# Alim.net
KiCad netlist of a schematic drawn in Altium Designer
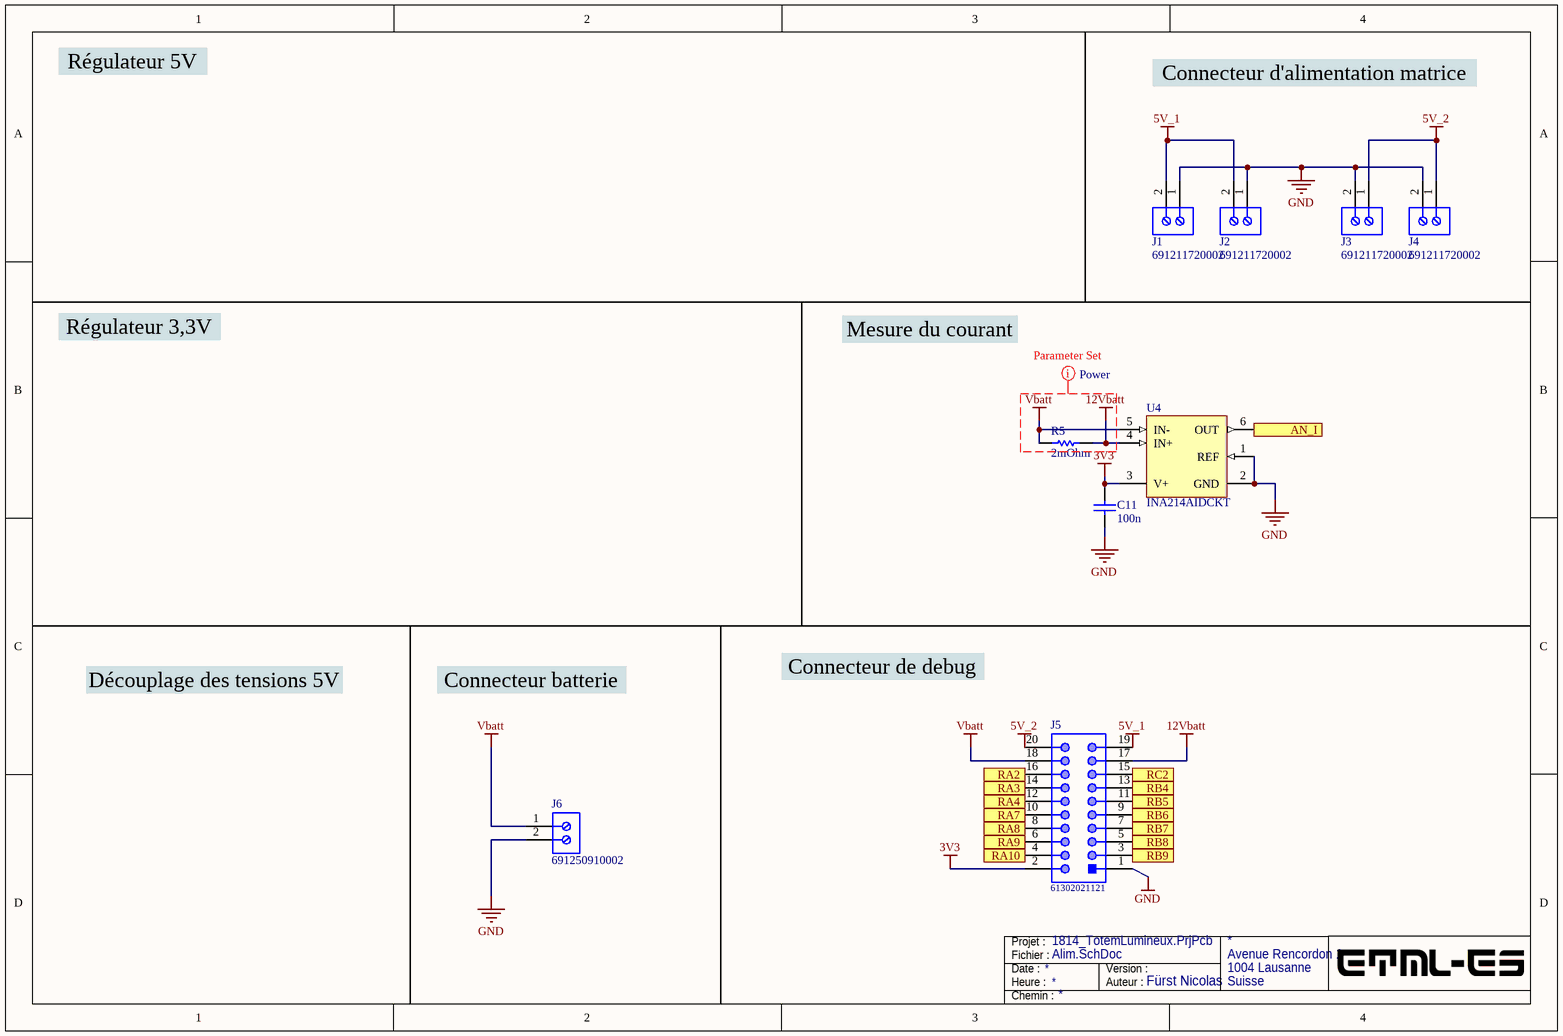
[diagram p0: Alim.SchDoc]

(export (version "E")
  (design (tool "Eeschema 10.0.6"))
  (components
    (comp (ref "C11")
      (value "100n")
      (footprint "CAPC0805(2012)155_L")
      (fields (field (name "TOLERANCE") "Â±10%"))
      (libsource (lib "Schlib1") (part "Capa"))
    )
    (comp (ref "J1")
      (value "691211720002")
      (footprint "691211720002")
      (description "Serie 211 - 5.00 mm 45deg Entry Modular with Rising Cage Clamp - 15.50 mm Height WR-TBL, 2 pin")
      (fields (field (name "MANUFACTURER") "Wurth Elektronik") (field (name "PUBLISHER") "WurthElektronik"))
      (libsource (lib "Altium Content Vault") (part "WE-CN-1P-F-TB2"))
    )
    (comp (ref "J2")
      (value "691211720002")
      (footprint "691211720002")
      (description "Serie 211 - 5.00 mm 45deg Entry Modular with Rising Cage Clamp - 15.50 mm Height WR-TBL, 2 pin")
      (fields (field (name "MANUFACTURER") "Wurth Elektronik") (field (name "PUBLISHER") "WurthElektronik"))
      (libsource (lib "Altium Content Vault") (part "WE-CN-1P-F-TB2"))
    )
    (comp (ref "J3")
      (value "691211720002")
      (footprint "691211720002")
      (description "Serie 211 - 5.00 mm 45deg Entry Modular with Rising Cage Clamp - 15.50 mm Height WR-TBL, 2 pin")
      (fields (field (name "MANUFACTURER") "Wurth Elektronik") (field (name "PUBLISHER") "WurthElektronik"))
      (libsource (lib "Altium Content Vault") (part "WE-CN-1P-F-TB2"))
    )
    (comp (ref "J4")
      (value "691211720002")
      (footprint "691211720002")
      (description "Serie 211 - 5.00 mm 45deg Entry Modular with Rising Cage Clamp - 15.50 mm Height WR-TBL, 2 pin")
      (fields (field (name "MANUFACTURER") "Wurth Elektronik") (field (name "PUBLISHER") "WurthElektronik"))
      (libsource (lib "Altium Content Vault") (part "WE-CN-1P-F-TB2"))
    )
    (comp (ref "J5")
      (value "61302021121")
      (footprint "61302021121")
      (description "THT Vertical Pin Header WR-PHD, Pitch 2.54 mm, Dual Row, 20 pins")
      (fields (field (name "MANUFACTURER") "Wurth Elektronik") (field (name "PUBLISHER") "WurthElektronik"))
      (libsource (lib "Altium Content Vault") (part "WE-CN-2P-M-R20"))
    )
    (comp (ref "J6")
      (value "691250910002")
      (footprint "691250910002")
      (description "Serie 2509 - 9.52 mm Horizontal Entry Modular with Rising Cage Clamp WR-TBL, 2 pin")
      (fields (field (name "MANUFACTURER") "Wurth Elektronik") (field (name "PUBLISHER") "WurthElektronik"))
      (libsource (lib "Altium Content Vault") (part "WE-CN-1P-F-TB2"))
    )
    (comp (ref "R5")
      (value "2mOhm")
      (footprint "RESC1206(3216)_N")
      (fields (field (name "POWER") "0.125 W") (field (name "TOLERANCE") "1 %"))
      (libsource (lib "Schlib1") (part "Resistor"))
    )
    (comp (ref "U4")
      (value "INA214AIDCKT")
      (footprint "DCK0006A_N")
      (fields (field (name "MANUFACTURER") "TexasInstruments"))
      (libsource (lib "Schlib1") (part "CMP-2000-06456-1"))
    )
  )
  (nets
    (net (code "1") (name "/AN_I") (class "Default")
      (node (ref "U4") (pin "6") (pinfunction "OUT_6") (pintype "output"))
    )
    (net (code "2") (name "/RA2") (class "Default")
      (node (ref "J5") (pin "16") (pinfunction "16_16") (pintype "passive"))
    )
    (net (code "3") (name "/RA3") (class "Default")
      (node (ref "J5") (pin "14") (pinfunction "14_14") (pintype "passive"))
    )
    (net (code "4") (name "/RA4") (class "Default")
      (node (ref "J5") (pin "12") (pinfunction "12_12") (pintype "passive"))
    )
    (net (code "5") (name "/RA7") (class "Default")
      (node (ref "J5") (pin "10") (pinfunction "10_10") (pintype "passive"))
    )
    (net (code "6") (name "/RA8") (class "Default")
      (node (ref "J5") (pin "8") (pinfunction "8_8") (pintype "passive"))
    )
    (net (code "7") (name "/RA9") (class "Default")
      (node (ref "J5") (pin "6") (pinfunction "6_6") (pintype "passive"))
    )
    (net (code "8") (name "/RA10") (class "Default")
      (node (ref "J5") (pin "4") (pinfunction "4_4") (pintype "passive"))
    )
    (net (code "9") (name "/RB4") (class "Default")
      (node (ref "J5") (pin "13") (pinfunction "13_13") (pintype "passive"))
    )
    (net (code "10") (name "/RB5") (class "Default")
      (node (ref "J5") (pin "11") (pinfunction "11_11") (pintype "passive"))
    )
    (net (code "11") (name "/RB6") (class "Default")
      (node (ref "J5") (pin "9") (pinfunction "9_9") (pintype "passive"))
    )
    (net (code "12") (name "/RB7") (class "Default")
      (node (ref "J5") (pin "7") (pinfunction "7_7") (pintype "passive"))
    )
    (net (code "13") (name "/RB8") (class "Default")
      (node (ref "J5") (pin "5") (pinfunction "5_5") (pintype "passive"))
    )
    (net (code "14") (name "/RB9") (class "Default")
      (node (ref "J5") (pin "3") (pinfunction "3_3") (pintype "passive"))
    )
    (net (code "15") (name "/RC2") (class "Default")
      (node (ref "J5") (pin "15") (pinfunction "15_15") (pintype "passive"))
    )
    (net (code "16") (name "3V3") (class "Default")
      (node (ref "C11") (pin "1") (pinfunction "1_1") (pintype "passive"))
      (node (ref "J5") (pin "2") (pinfunction "2_2") (pintype "passive"))
      (node (ref "U4") (pin "3") (pinfunction "V+_3") (pintype "power_in"))
    )
    (net (code "17") (name "5V_1") (class "Default")
      (node (ref "J1") (pin "2") (pinfunction "2_2") (pintype "passive"))
      (node (ref "J2") (pin "2") (pinfunction "2_2") (pintype "passive"))
      (node (ref "J5") (pin "19") (pinfunction "19_19") (pintype "passive"))
    )
    (net (code "18") (name "5V_2") (class "Default")
      (node (ref "J3") (pin "1") (pinfunction "1_1") (pintype "passive"))
      (node (ref "J4") (pin "1") (pinfunction "1_1") (pintype "passive"))
      (node (ref "J5") (pin "20") (pinfunction "20_20") (pintype "passive"))
    )
    (net (code "19") (name "12Vbatt") (class "Default")
      (node (ref "J5") (pin "17") (pinfunction "17_17") (pintype "passive"))
      (node (ref "R5") (pin "1") (pinfunction "1_1") (pintype "passive"))
      (node (ref "U4") (pin "4") (pinfunction "IN+_4") (pintype "input"))
    )
    (net (code "20") (name "GND") (class "Default")
      (node (ref "C11") (pin "2") (pinfunction "2_2") (pintype "passive"))
      (node (ref "J1") (pin "1") (pinfunction "1_1") (pintype "passive"))
      (node (ref "J2") (pin "1") (pinfunction "1_1") (pintype "passive"))
      (node (ref "J3") (pin "2") (pinfunction "2_2") (pintype "passive"))
      (node (ref "J4") (pin "2") (pinfunction "2_2") (pintype "passive"))
      (node (ref "J5") (pin "1") (pinfunction "1_1") (pintype "passive"))
      (node (ref "J6") (pin "2") (pinfunction "2_2") (pintype "passive"))
      (node (ref "U4") (pin "1") (pinfunction "REF_1") (pintype "input"))
      (node (ref "U4") (pin "2") (pinfunction "GND_2") (pintype "power_in"))
    )
    (net (code "21") (name "Vbatt") (class "Default")
      (node (ref "J5") (pin "18") (pinfunction "18_18") (pintype "passive"))
      (node (ref "J6") (pin "1") (pinfunction "1_1") (pintype "passive"))
      (node (ref "R5") (pin "2") (pinfunction "2_2") (pintype "passive"))
      (node (ref "U4") (pin "5") (pinfunction "IN-_5") (pintype "input"))
    )
  )
)
